# Dot.net
KiCad netlist of a schematic drawn in EAGLE
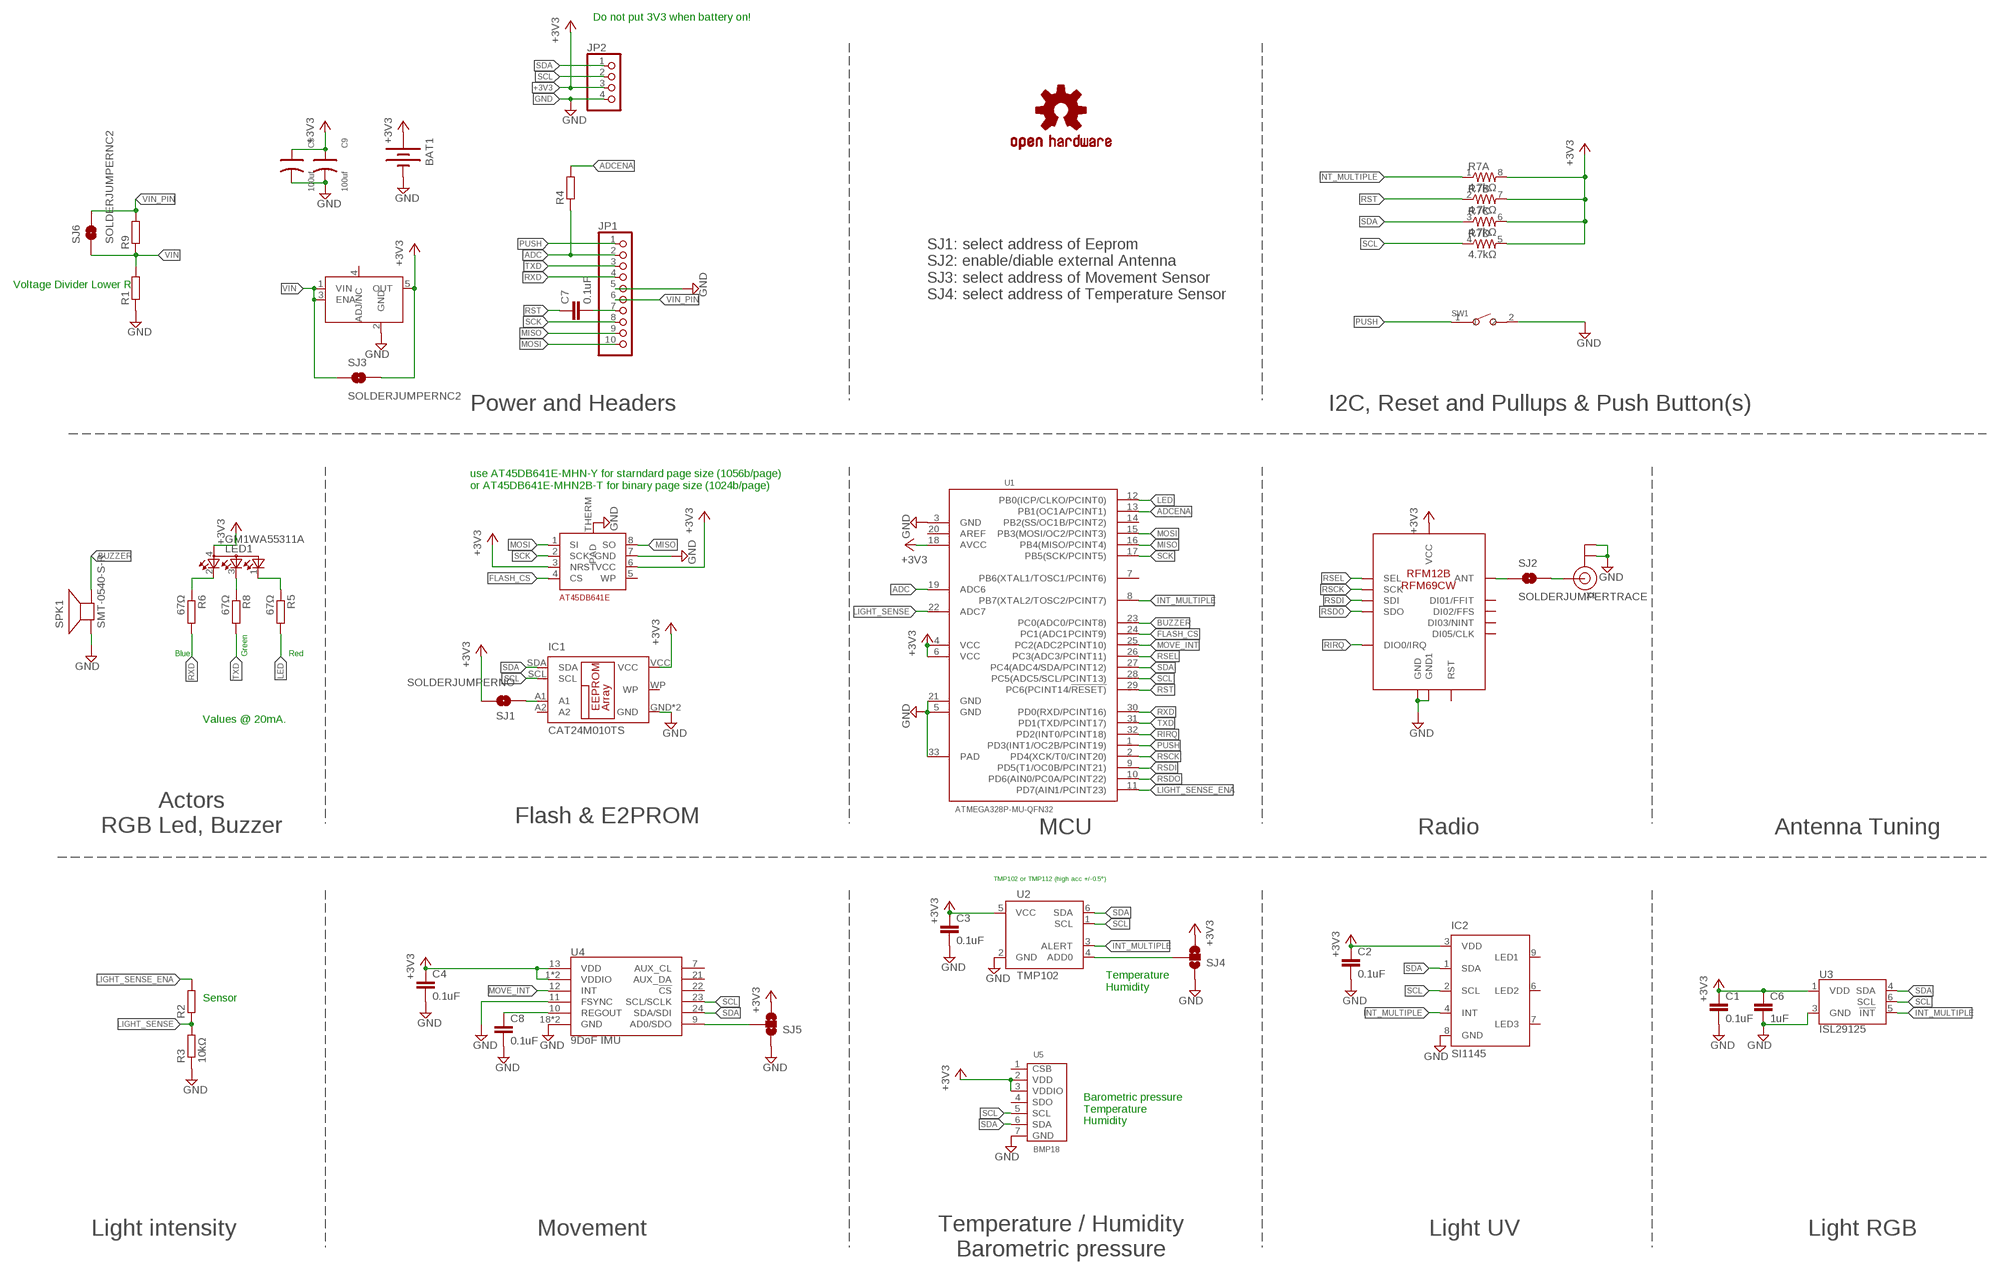
[diagram p0: schematic, sheet 1]
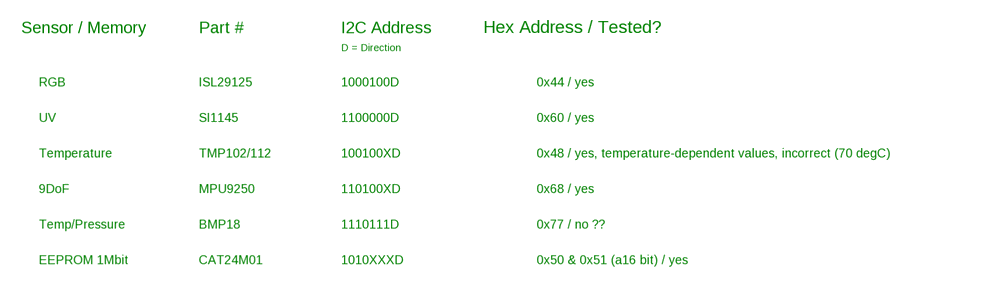
[diagram p1: schematic, sheet 2]
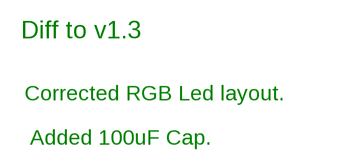
[diagram p2: schematic, sheet 3]

(export (version "E")
  (design (tool "Eeschema 10.0.6"))
  (components
    (comp (ref "BAT1")
      (value "BATTERY20PTH")
      (footprint "eagle-import:BATTCOM_20MM_PTH")
      (libsource (lib "eagle-import") (part "BATTERY20PTH"))
    )
    (comp (ref "C1")
      (value "0.1uF")
      (footprint "eagle-import:C0603")
      (libsource (lib "eagle-import") (part "C-EUC0603"))
    )
    (comp (ref "C2")
      (value "0.1uF")
      (footprint "eagle-import:C0603")
      (libsource (lib "eagle-import") (part "C-EUC0603"))
    )
    (comp (ref "C3")
      (value "0.1uF")
      (footprint "eagle-import:C0603")
      (libsource (lib "eagle-import") (part "C-EUC0603"))
    )
    (comp (ref "C4")
      (value "0.1uF")
      (footprint "eagle-import:C0603")
      (libsource (lib "eagle-import") (part "C-EUC0603"))
    )
    (comp (ref "C5")
      (value "100uf")
      (footprint "eagle-import:AVX-A")
      (fields (field (name "MPN") "TLJA107M006R0800"))
      (libsource (lib "eagle-import") (part "TANTALUM-SMD-100UF-6.3V(AVX-A)"))
    )
    (comp (ref "C6")
      (value "1uF")
      (footprint "eagle-import:C0603")
      (libsource (lib "eagle-import") (part "C-EUC0603"))
    )
    (comp (ref "C7")
      (value "0.1uF")
      (footprint "eagle-import:C0603")
      (libsource (lib "eagle-import") (part "C-EUC0603"))
    )
    (comp (ref "C8")
      (value "0.1uF")
      (footprint "eagle-import:C0603")
      (libsource (lib "eagle-import") (part "C-EUC0603"))
    )
    (comp (ref "C9")
      (value "100uf")
      (footprint "eagle-import:AVX-A")
      (fields (field (name "MPN") "TLJA107M006R0800"))
      (libsource (lib "eagle-import") (part "TANTALUM-SMD-100UF-6.3V(AVX-A)"))
    )
    (comp (ref "IC1")
      (value "CAT24M010TS")
      (footprint "eagle-import:TSSOP8")
      (fields (field (name "MF") "On Semiconductor") (field (name "MPN") "24C00T-E/ST"))
      (libsource (lib "eagle-import") (part "CAT24M01TS0"))
    )
    (comp (ref "IC2")
      (value "SI1145")
      (footprint "eagle-import:QFN-10")
      (libsource (lib "eagle-import") (part "SI1145"))
    )
    (comp (ref "JP1")
      (value "PINHD-1X10")
      (footprint "eagle-import:1X10")
      (libsource (lib "eagle-import") (part "PINHD-1X10"))
    )
    (comp (ref "JP2")
      (value "PINHD-1X4")
      (footprint "eagle-import:1X04")
      (libsource (lib "eagle-import") (part "PINHD-1X4"))
    )
    (comp (ref "LED1")
      (value "GM1WA55311A")
      (footprint "eagle-import:GM1WA55311A")
      (libsource (lib "eagle-import") (part "GM1WA55311A"))
    )
    (comp (ref "LOGO1")
      (value "OSHW-LOGOS")
      (footprint "eagle-import:OSHW-LOGO-S")
      (libsource (lib "eagle-import") (part "OSHW-LOGOS"))
    )
    (comp (ref "R1")
      (value "R-EU_R0603")
      (footprint "eagle-import:R0603")
      (libsource (lib "eagle-import") (part "R-EU_R0603"))
    )
    (comp (ref "R2")
      (value "R-EU_R0805")
      (footprint "eagle-import:R0805")
      (libsource (lib "eagle-import") (part "R-EU_R0805"))
    )
    (comp (ref "R3")
      (value "10kΩ")
      (footprint "eagle-import:R0603")
      (libsource (lib "eagle-import") (part "R-EU_R0603"))
    )
    (comp (ref "R4")
      (value "R-EU_R0603")
      (footprint "eagle-import:R0603")
      (libsource (lib "eagle-import") (part "R-EU_R0603"))
    )
    (comp (ref "R5")
      (value "67Ω")
      (footprint "eagle-import:R0603")
      (libsource (lib "eagle-import") (part "R-EU_R0603"))
    )
    (comp (ref "R6")
      (value "67Ω")
      (footprint "eagle-import:R0603")
      (libsource (lib "eagle-import") (part "R-EU_R0603"))
    )
    (comp (ref "R7")
      (value "4.7kΩ")
      (footprint "eagle-import:0603-ARV")
      (libsource (lib "eagle-import") (part "RESISTOR-ARRAY0603-ARV"))
    )
    (comp (ref "R8")
      (value "67Ω")
      (footprint "eagle-import:R0603")
      (libsource (lib "eagle-import") (part "R-EU_R0603"))
    )
    (comp (ref "R9")
      (value "R-EU_R0603")
      (footprint "eagle-import:R0603")
      (libsource (lib "eagle-import") (part "R-EU_R0603"))
    )
    (comp (ref "SJ1")
      (value "SOLDERJUMPERNO")
      (footprint "eagle-import:SJ_2S-NO")
      (libsource (lib "eagle-import") (part "SOLDERJUMPERNO"))
    )
    (comp (ref "SJ2")
      (value "SOLDERJUMPERTRACE")
      (footprint "eagle-import:SJ_2S-TRACE")
      (libsource (lib "eagle-import") (part "SOLDERJUMPERTRACE"))
    )
    (comp (ref "SJ3")
      (value "SOLDERJUMPERNC2")
      (footprint "eagle-import:SJ_2S-NOTRACE")
      (libsource (lib "eagle-import") (part "SOLDERJUMPERNC2"))
    )
    (comp (ref "SJ4")
      (value "SOLDERJUMPER_2WAYS")
      (footprint "eagle-import:SJ_3")
      (libsource (lib "eagle-import") (part "SOLDERJUMPER_2WAYS"))
    )
    (comp (ref "SJ5")
      (value "SOLDERJUMPER_2WAYS")
      (footprint "eagle-import:SJ_3")
      (libsource (lib "eagle-import") (part "SOLDERJUMPER_2WAYS"))
    )
    (comp (ref "SJ6")
      (value "SOLDERJUMPERNC2")
      (footprint "eagle-import:SJ_2S-NOTRACE")
      (libsource (lib "eagle-import") (part "SOLDERJUMPERNC2"))
    )
    (comp (ref "SPK1")
      (value "SMT-0540-S-R")
      (footprint "eagle-import:SMT-0540-S-R")
      (libsource (lib "eagle-import") (part "SMT-0540-S-R"))
    )
    (comp (ref "SW1")
      (value "SMD-BUTTON(2P-6.0X3.0X2.5MM)-DHT-1163S")
      (footprint "eagle-import:SW2-4.0-6.0X3.0X2.5MM")
      (libsource (lib "eagle-import") (part "SMD-BUTTON(2P-6.0X3.0X2.5MM)-DHT-1163S"))
    )
    (comp (ref "U$1")
      (value "RFM12B/69CW")
      (footprint "eagle-import:RFM12B_69CW")
      (libsource (lib "eagle-import") (part "RFM12B/69CW"))
    )
    (comp (ref "U$3")
      (value "AT45DB641E")
      (footprint "eagle-import:UDFN-8")
      (libsource (lib "eagle-import") (part "AT45DB641E"))
    )
    (comp (ref "U$4")
      (value "LDCL015")
      (footprint "eagle-import:SOT23-5")
      (libsource (lib "eagle-import") (part "LDCL015"))
    )
    (comp (ref "U1")
      (value "ATMEGA328P-MU-QFN32")
      (footprint "eagle-import:QFN32G-0.5-5X5MM")
      (fields (field (name "MPN") "ATMEGA328P-MU"))
      (libsource (lib "eagle-import") (part "MCU-ATMEGA328P-MU(QFN32)"))
    )
    (comp (ref "U2")
      (value "TMP102")
      (footprint "eagle-import:SOT563")
      (libsource (lib "eagle-import") (part "TMP102"))
    )
    (comp (ref "U3")
      (value "ISL29125")
      (footprint "eagle-import:ODFN-6")
      (libsource (lib "eagle-import") (part "ISL29125"))
    )
    (comp (ref "U4")
      (value "9DoF IMU")
      (footprint "eagle-import:QFN24-3X3")
      (libsource (lib "eagle-import") (part "MPU-9250"))
    )
    (comp (ref "U5")
      (value "BMP18")
      (footprint "eagle-import:LGA7-1.5-3.8X3.6MM")
      (libsource (lib "eagle-import") (part "PRESSURE-BMP180(LGA7)"))
    )
    (comp (ref "X1")
      (value "ANTENNA_U.FL")
      (footprint "eagle-import:U.FL")
      (libsource (lib "eagle-import") (part "ANTENNA_U.FL"))
    )
  )
  (nets
    (net (code "1") (name "+3V3") (class "Default")
      (node (ref "BAT1") (pin "1") (pinfunction "+_1") (pintype "power_in"))
      (node (ref "C1") (pin "1") (pinfunction "1_1") (pintype "passive"))
      (node (ref "C2") (pin "1") (pinfunction "1_1") (pintype "passive"))
      (node (ref "C3") (pin "1") (pinfunction "1_1") (pintype "passive"))
      (node (ref "C4") (pin "1") (pinfunction "1_1") (pintype "passive"))
      (node (ref "C5") (pin "+") (pinfunction "+_+") (pintype "passive"))
      (node (ref "C6") (pin "1") (pinfunction "1_1") (pintype "passive"))
      (node (ref "C9") (pin "+") (pinfunction "+_+") (pintype "passive"))
      (node (ref "IC1") (pin "VCC") (pinfunction "VCC_VCC") (pintype "power_in"))
      (node (ref "IC2") (pin "3") (pinfunction "VDD_3") (pintype "power_in"))
      (node (ref "JP2") (pin "3") (pinfunction "3_3") (pintype "passive"))
      (node (ref "LED1") (pin "4") (pinfunction "A_4") (pintype "passive"))
      (node (ref "R7") (pin "5") (pinfunction "2_5") (pintype "passive"))
      (node (ref "R7") (pin "6") (pinfunction "2_6") (pintype "passive"))
      (node (ref "R7") (pin "7") (pinfunction "2_7") (pintype "passive"))
      (node (ref "R7") (pin "8") (pinfunction "2_8") (pintype "passive"))
      (node (ref "SJ1") (pin "2") (pinfunction "2_2") (pintype "passive"))
      (node (ref "SJ3") (pin "2") (pinfunction "2_2") (pintype "passive"))
      (node (ref "SJ4") (pin "3") (pinfunction "3_3") (pintype "passive"))
      (node (ref "SJ5") (pin "3") (pinfunction "3_3") (pintype "passive"))
      (node (ref "U$1") (pin "VDD") (pinfunction "VCC_VDD") (pintype "power_in"))
      (node (ref "U$3") (pin "3") (pinfunction "NRST_3") (pintype "bidirectional"))
      (node (ref "U$3") (pin "6") (pinfunction "VCC_6") (pintype "bidirectional"))
      (node (ref "U$4") (pin "5") (pinfunction "OUT_5") (pintype "bidirectional"))
      (node (ref "U1") (pin "18") (pinfunction "AVCC_18") (pintype "bidirectional"))
      (node (ref "U1") (pin "4") (pinfunction "VCC_4") (pintype "bidirectional"))
      (node (ref "U1") (pin "6") (pinfunction "VCC_6") (pintype "bidirectional"))
      (node (ref "U2") (pin "5") (pinfunction "VCC_5") (pintype "bidirectional"))
      (node (ref "U3") (pin "1") (pinfunction "VDD_1") (pintype "bidirectional"))
      (node (ref "U4") (pin "1") (pinfunction "VDDIO_1") (pintype "bidirectional"))
      (node (ref "U4") (pin "13") (pinfunction "VDD_13") (pintype "bidirectional"))
      (node (ref "U4") (pin "8") (pinfunction "VDDIO_8") (pintype "bidirectional"))
      (node (ref "U5") (pin "2") (pinfunction "VDD_2") (pintype "bidirectional"))
      (node (ref "U5") (pin "3") (pinfunction "VDDIO_3") (pintype "bidirectional"))
    )
    (net (code "2") (name "ADC") (class "Default")
      (node (ref "JP1") (pin "2") (pinfunction "2_2") (pintype "passive"))
      (node (ref "R4") (pin "1") (pinfunction "1_1") (pintype "passive"))
      (node (ref "U1") (pin "19") (pinfunction "ADC6_19") (pintype "bidirectional"))
    )
    (net (code "3") (name "ADCENA") (class "Default")
      (node (ref "R4") (pin "2") (pinfunction "2_2") (pintype "passive"))
      (node (ref "U1") (pin "13") (pinfunction "PB1(OC1A/PCINT1)_13") (pintype "bidirectional"))
    )
    (net (code "4") (name "BUZZER") (class "Default")
      (node (ref "SPK1") (pin "+") (pinfunction "-_+") (pintype "passive"))
      (node (ref "U1") (pin "23") (pinfunction "PC0(ADC0/PCINT8)_23") (pintype "bidirectional"))
    )
    (net (code "5") (name "FLASH_CS") (class "Default")
      (node (ref "U$3") (pin "4") (pinfunction "CS_4") (pintype "bidirectional"))
      (node (ref "U1") (pin "24") (pinfunction "PC1(ADC1PCINT9)_24") (pintype "bidirectional"))
    )
    (net (code "6") (name "GND") (class "Default")
      (node (ref "BAT1") (pin "2") (pinfunction "-_2") (pintype "power_in"))
      (node (ref "C1") (pin "2") (pinfunction "2_2") (pintype "passive"))
      (node (ref "C2") (pin "2") (pinfunction "2_2") (pintype "passive"))
      (node (ref "C3") (pin "2") (pinfunction "2_2") (pintype "passive"))
      (node (ref "C4") (pin "2") (pinfunction "2_2") (pintype "passive"))
      (node (ref "C5") (pin "-") (pinfunction "-_-") (pintype "passive"))
      (node (ref "C6") (pin "2") (pinfunction "2_2") (pintype "passive"))
      (node (ref "C8") (pin "2") (pinfunction "2_2") (pintype "passive"))
      (node (ref "C9") (pin "-") (pinfunction "-_-") (pintype "passive"))
      (node (ref "IC1") (pin "GND") (pinfunction "GND_GND") (pintype "power_in"))
      (node (ref "IC1") (pin "NC") (pinfunction "GND_NC") (pintype "power_in"))
      (node (ref "IC2") (pin "8") (pinfunction "GND_8") (pintype "power_in"))
      (node (ref "JP1") (pin "5") (pinfunction "5_5") (pintype "passive"))
      (node (ref "JP2") (pin "4") (pinfunction "4_4") (pintype "passive"))
      (node (ref "R1") (pin "1") (pinfunction "1_1") (pintype "passive"))
      (node (ref "R3") (pin "1") (pinfunction "1_1") (pintype "passive"))
      (node (ref "SJ4") (pin "1") (pinfunction "1_1") (pintype "passive"))
      (node (ref "SJ5") (pin "1") (pinfunction "1_1") (pintype "passive"))
      (node (ref "SPK1") (pin "-") (pinfunction "+_-") (pintype "passive"))
      (node (ref "SW1") (pin "2") (pinfunction "2_2") (pintype "bidirectional"))
      (node (ref "U$1") (pin "GND") (pinfunction "GND_GND") (pintype "power_in"))
      (node (ref "U$1") (pin "GND1") (pinfunction "GND1_GND1") (pintype "power_in"))
      (node (ref "U$3") (pin "7") (pinfunction "GND_7") (pintype "bidirectional"))
      (node (ref "U$3") (pin "THERM") (pinfunction "PAD_THERM") (pintype "bidirectional"))
      (node (ref "U$4") (pin "2") (pinfunction "GND_2") (pintype "bidirectional"))
      (node (ref "U1") (pin "21") (pinfunction "GND_21") (pintype "bidirectional"))
      (node (ref "U1") (pin "3") (pinfunction "GND_3") (pintype "bidirectional"))
      (node (ref "U1") (pin "33") (pinfunction "PAD_33") (pintype "bidirectional"))
      (node (ref "U1") (pin "5") (pinfunction "GND_5") (pintype "bidirectional"))
      (node (ref "U2") (pin "2") (pinfunction "GND_2") (pintype "bidirectional"))
      (node (ref "U3") (pin "3") (pinfunction "GND_3") (pintype "bidirectional"))
      (node (ref "U4") (pin "11") (pinfunction "FSYNC_11") (pintype "bidirectional"))
      (node (ref "U4") (pin "18") (pinfunction "GND_18") (pintype "bidirectional"))
      (node (ref "U4") (pin "20") (pinfunction "GND_20") (pintype "bidirectional"))
      (node (ref "U5") (pin "7") (pinfunction "GND_7") (pintype "bidirectional"))
      (node (ref "X1") (pin "1") (pinfunction "GND_1") (pintype "passive"))
      (node (ref "X1") (pin "2") (pinfunction "GND_2") (pintype "passive"))
    )
    (net (code "7") (name "INT_MULTIPLE") (class "Default")
      (node (ref "IC2") (pin "4") (pinfunction "INT_4") (pintype "open_collector"))
      (node (ref "R7") (pin "1") (pinfunction "1_1") (pintype "passive"))
      (node (ref "U1") (pin "8") (pinfunction "PB7(XTAL2/TOSC2/PCINT7)_8") (pintype "bidirectional"))
      (node (ref "U2") (pin "3") (pinfunction "ALERT_3") (pintype "bidirectional"))
      (node (ref "U3") (pin "5") (pinfunction "~{INT}_5") (pintype "bidirectional"))
    )
    (net (code "8") (name "LED") (class "Default")
      (node (ref "R5") (pin "2") (pinfunction "2_2") (pintype "passive"))
      (node (ref "U1") (pin "12") (pinfunction "PB0(ICP/CLKO/PCINT0)_12") (pintype "bidirectional"))
    )
    (net (code "9") (name "LIGHT_SENSE") (class "Default")
      (node (ref "R2") (pin "1") (pinfunction "1_1") (pintype "passive"))
      (node (ref "R3") (pin "2") (pinfunction "2_2") (pintype "passive"))
      (node (ref "U1") (pin "22") (pinfunction "ADC7_22") (pintype "bidirectional"))
    )
    (net (code "10") (name "LIGHT_SENSE_ENA") (class "Default")
      (node (ref "R2") (pin "2") (pinfunction "2_2") (pintype "passive"))
      (node (ref "U1") (pin "11") (pinfunction "PD7(AIN1/PCINT23)_11") (pintype "bidirectional"))
    )
    (net (code "11") (name "MISO") (class "Default")
      (node (ref "JP1") (pin "9") (pinfunction "9_9") (pintype "passive"))
      (node (ref "U$3") (pin "8") (pinfunction "SO_8") (pintype "bidirectional"))
      (node (ref "U1") (pin "16") (pinfunction "PB4(MISO/PCINT4)_16") (pintype "bidirectional"))
    )
    (net (code "12") (name "MOSI") (class "Default")
      (node (ref "JP1") (pin "10") (pinfunction "10_10") (pintype "passive"))
      (node (ref "U$3") (pin "1") (pinfunction "SI_1") (pintype "bidirectional"))
      (node (ref "U1") (pin "15") (pinfunction "PB3(MOSI/OC2/PCINT3)_15") (pintype "bidirectional"))
    )
    (net (code "13") (name "MOVE_INT") (class "Default")
      (node (ref "U1") (pin "25") (pinfunction "PC2(ADC2PCINT10)_25") (pintype "bidirectional"))
      (node (ref "U4") (pin "12") (pinfunction "INT_12") (pintype "bidirectional"))
    )
    (net (code "14") (name "Net-(C7-Pad2)") (class "Default")
      (node (ref "C7") (pin "2") (pinfunction "2_2") (pintype "passive"))
      (node (ref "JP1") (pin "7") (pinfunction "7_7") (pintype "passive"))
    )
    (net (code "15") (name "Net-(IC1-PadA1)") (class "Default")
      (node (ref "IC1") (pin "A1") (pinfunction "A1_A1") (pintype "bidirectional"))
      (node (ref "SJ1") (pin "1") (pinfunction "1_1") (pintype "passive"))
    )
    (net (code "16") (name "Net-(LED1-CBLUE)") (class "Default")
      (node (ref "LED1") (pin "3") (pinfunction "CBLUE_3") (pintype "passive"))
      (node (ref "R8") (pin "1") (pinfunction "1_1") (pintype "passive"))
    )
    (net (code "17") (name "Net-(LED1-CGREEN)") (class "Default")
      (node (ref "LED1") (pin "1") (pinfunction "CGREEN_1") (pintype "passive"))
      (node (ref "R5") (pin "1") (pinfunction "1_1") (pintype "passive"))
    )
    (net (code "18") (name "Net-(LED1-CRED)") (class "Default")
      (node (ref "LED1") (pin "2") (pinfunction "CRED_2") (pintype "passive"))
      (node (ref "R6") (pin "1") (pinfunction "1_1") (pintype "passive"))
    )
    (net (code "19") (name "Net-(SJ2-Pad1)") (class "Default")
      (node (ref "SJ2") (pin "1") (pinfunction "1_1") (pintype "passive"))
      (node (ref "U$1") (pin "ANT") (pinfunction "ANT_ANT") (pintype "passive"))
    )
    (net (code "20") (name "Net-(U2-ADD0)") (class "Default")
      (node (ref "SJ4") (pin "2") (pinfunction "2_2") (pintype "passive"))
      (node (ref "U2") (pin "4") (pinfunction "ADD0_4") (pintype "bidirectional"))
    )
    (net (code "21") (name "Net-(U4-AD0{slash}SDO)") (class "Default")
      (node (ref "SJ5") (pin "2") (pinfunction "2_2") (pintype "passive"))
      (node (ref "U4") (pin "9") (pinfunction "AD0/SDO_9") (pintype "bidirectional"))
    )
    (net (code "22") (name "Net-(U4-REGOUT)") (class "Default")
      (node (ref "C8") (pin "1") (pinfunction "1_1") (pintype "passive"))
      (node (ref "U4") (pin "10") (pinfunction "REGOUT_10") (pintype "bidirectional"))
    )
    (net (code "23") (name "Net-(X1-SIGNAL)") (class "Default")
      (node (ref "SJ2") (pin "2") (pinfunction "2_2") (pintype "passive"))
      (node (ref "X1") (pin "3") (pinfunction "SIGNAL_3") (pintype "passive"))
    )
    (net (code "24") (name "PUSH") (class "Default")
      (node (ref "JP1") (pin "1") (pinfunction "1_1") (pintype "passive"))
      (node (ref "SW1") (pin "1") (pinfunction "1_1") (pintype "bidirectional"))
      (node (ref "U1") (pin "1") (pinfunction "PD3(INT1/OC2B/PCINT19)_1") (pintype "bidirectional"))
    )
    (net (code "25") (name "RIRQ") (class "Default")
      (node (ref "U$1") (pin "IRQ") (pinfunction "DIO0/IRQ_IRQ") (pintype "open_collector"))
      (node (ref "U1") (pin "32") (pinfunction "PD2(INT0/PCINT18)_32") (pintype "bidirectional"))
    )
    (net (code "26") (name "RSCK") (class "Default")
      (node (ref "U$1") (pin "SCK") (pinfunction "SCK_SCK") (pintype "input"))
      (node (ref "U1") (pin "2") (pinfunction "PD4(XCK/T0/CINT20)_2") (pintype "bidirectional"))
    )
    (net (code "27") (name "RSDI") (class "Default")
      (node (ref "U$1") (pin "SDI") (pinfunction "SDI_SDI") (pintype "input"))
      (node (ref "U1") (pin "9") (pinfunction "PD5(T1/OC0B/PCINT21)_9") (pintype "bidirectional"))
    )
    (net (code "28") (name "RSDO") (class "Default")
      (node (ref "U$1") (pin "SDO") (pinfunction "SDO_SDO") (pintype "output"))
      (node (ref "U1") (pin "10") (pinfunction "PD6(AIN0/PC0A/PCINT22)_10") (pintype "bidirectional"))
    )
    (net (code "29") (name "RSEL") (class "Default")
      (node (ref "U$1") (pin "SEL") (pinfunction "SEL_SEL") (pintype "input"))
      (node (ref "U1") (pin "26") (pinfunction "PC3(ADC3/PCINT11)_26") (pintype "bidirectional"))
    )
    (net (code "30") (name "RST") (class "Default")
      (node (ref "C7") (pin "1") (pinfunction "1_1") (pintype "passive"))
      (node (ref "R7") (pin "2") (pinfunction "1_2") (pintype "passive"))
      (node (ref "U1") (pin "29") (pinfunction "PC6(PCINT14/~{RESET})_29") (pintype "bidirectional"))
    )
    (net (code "31") (name "RXD") (class "Default")
      (node (ref "JP1") (pin "4") (pinfunction "4_4") (pintype "passive"))
      (node (ref "R6") (pin "2") (pinfunction "2_2") (pintype "passive"))
      (node (ref "U1") (pin "30") (pinfunction "PD0(RXD/PCINT16)_30") (pintype "bidirectional"))
    )
    (net (code "32") (name "SCK") (class "Default")
      (node (ref "JP1") (pin "8") (pinfunction "8_8") (pintype "passive"))
      (node (ref "U$3") (pin "2") (pinfunction "SCK_2") (pintype "bidirectional"))
      (node (ref "U1") (pin "17") (pinfunction "PB5(SCK/PCINT5)_17") (pintype "bidirectional"))
    )
    (net (code "33") (name "SCL") (class "Default")
      (node (ref "IC1") (pin "SCL") (pinfunction "SCL_SCL") (pintype "input"))
      (node (ref "IC2") (pin "2") (pinfunction "SCL_2") (pintype "input"))
      (node (ref "JP2") (pin "2") (pinfunction "2_2") (pintype "passive"))
      (node (ref "R7") (pin "4") (pinfunction "1_4") (pintype "passive"))
      (node (ref "U1") (pin "28") (pinfunction "PC5(ADC5/SCL/PCINT13)_28") (pintype "bidirectional"))
      (node (ref "U2") (pin "1") (pinfunction "SCL_1") (pintype "bidirectional"))
      (node (ref "U3") (pin "6") (pinfunction "SCL_6") (pintype "bidirectional"))
      (node (ref "U4") (pin "23") (pinfunction "SCL/SCLK_23") (pintype "bidirectional"))
      (node (ref "U5") (pin "5") (pinfunction "SCL_5") (pintype "bidirectional"))
    )
    (net (code "34") (name "SDA") (class "Default")
      (node (ref "IC1") (pin "SDA") (pinfunction "SDA_SDA") (pintype "bidirectional"))
      (node (ref "IC2") (pin "1") (pinfunction "SDA_1") (pintype "bidirectional"))
      (node (ref "JP2") (pin "1") (pinfunction "1_1") (pintype "passive"))
      (node (ref "R7") (pin "3") (pinfunction "1_3") (pintype "passive"))
      (node (ref "U1") (pin "27") (pinfunction "PC4(ADC4/SDA/PCINT12)_27") (pintype "bidirectional"))
      (node (ref "U2") (pin "6") (pinfunction "SDA_6") (pintype "bidirectional"))
      (node (ref "U3") (pin "4") (pinfunction "SDA_4") (pintype "bidirectional"))
      (node (ref "U4") (pin "24") (pinfunction "SDA/SDI_24") (pintype "bidirectional"))
      (node (ref "U5") (pin "6") (pinfunction "SDA_6") (pintype "bidirectional"))
    )
    (net (code "35") (name "TXD") (class "Default")
      (node (ref "JP1") (pin "3") (pinfunction "3_3") (pintype "passive"))
      (node (ref "R8") (pin "2") (pinfunction "2_2") (pintype "passive"))
      (node (ref "U1") (pin "31") (pinfunction "PD1(TXD/PCINT17)_31") (pintype "bidirectional"))
    )
    (net (code "36") (name "VIN") (class "Default")
      (node (ref "R1") (pin "2") (pinfunction "2_2") (pintype "passive"))
      (node (ref "R9") (pin "1") (pinfunction "1_1") (pintype "passive"))
      (node (ref "SJ3") (pin "1") (pinfunction "1_1") (pintype "passive"))
      (node (ref "SJ6") (pin "1") (pinfunction "1_1") (pintype "passive"))
      (node (ref "U$4") (pin "1") (pinfunction "VIN_1") (pintype "bidirectional"))
      (node (ref "U$4") (pin "3") (pinfunction "ENA_3") (pintype "bidirectional"))
    )
    (net (code "37") (name "VIN_PIN") (class "Default")
      (node (ref "JP1") (pin "6") (pinfunction "6_6") (pintype "passive"))
      (node (ref "R9") (pin "2") (pinfunction "2_2") (pintype "passive"))
      (node (ref "SJ6") (pin "2") (pinfunction "2_2") (pintype "passive"))
    )
    (net (code "38") (name "unconnected-(IC1-PadA2)") (class "Default")
      (node (ref "IC1") (pin "A2") (pinfunction "A2_A2") (pintype "bidirectional"))
    )
    (net (code "39") (name "unconnected-(IC1-PadWP)") (class "Default")
      (node (ref "IC1") (pin "WP") (pinfunction "WP_WP") (pintype "bidirectional"))
    )
    (net (code "40") (name "unconnected-(IC2-LED1-Pad9)") (class "Default")
      (node (ref "IC2") (pin "9") (pinfunction "LED1_9") (pintype "output"))
    )
    (net (code "41") (name "unconnected-(IC2-LED2-Pad6)") (class "Default")
      (node (ref "IC2") (pin "6") (pinfunction "LED2_6") (pintype "output"))
    )
    (net (code "42") (name "unconnected-(IC2-LED3-Pad7)") (class "Default")
      (node (ref "IC2") (pin "7") (pinfunction "LED3_7") (pintype "output"))
    )
    (net (code "43") (name "unconnected-(U$1-DI01{slash}FFIT-PadFFIT)") (class "Default")
      (node (ref "U$1") (pin "FFIT") (pinfunction "DI01/FFIT_FFIT") (pintype "passive"))
    )
    (net (code "44") (name "unconnected-(U$1-DI02{slash}FFS-PadFFS)") (class "Default")
      (node (ref "U$1") (pin "FFS") (pinfunction "DI02/FFS_FFS") (pintype "bidirectional"))
    )
    (net (code "45") (name "unconnected-(U$1-DI03{slash}NINT-PadNINT)") (class "Default")
      (node (ref "U$1") (pin "NINT") (pinfunction "DI03/NINT_NINT") (pintype "passive"))
    )
    (net (code "46") (name "unconnected-(U$1-DI05{slash}CLK-PadCLK)") (class "Default")
      (node (ref "U$1") (pin "CLK") (pinfunction "DI05/CLK_CLK") (pintype "passive"))
    )
    (net (code "47") (name "unconnected-(U$1-PadRST)") (class "Default")
      (node (ref "U$1") (pin "RST") (pinfunction "RST_RST") (pintype "open_collector"))
    )
    (net (code "48") (name "unconnected-(U$3-WP-Pad5)") (class "Default")
      (node (ref "U$3") (pin "5") (pinfunction "WP_5") (pintype "bidirectional"))
    )
    (net (code "49") (name "unconnected-(U$4-ADJ{slash}NC-Pad4)") (class "Default")
      (node (ref "U$4") (pin "4") (pinfunction "ADJ/NC_4") (pintype "bidirectional"))
    )
    (net (code "50") (name "unconnected-(U1-AREF-Pad20)") (class "Default")
      (node (ref "U1") (pin "20") (pinfunction "AREF_20") (pintype "bidirectional"))
    )
    (net (code "51") (name "unconnected-(U1-PB2(SS{slash}OC1B{slash}PCINT2)-Pad14)") (class "Default")
      (node (ref "U1") (pin "14") (pinfunction "PB2(SS/OC1B/PCINT2)_14") (pintype "bidirectional"))
    )
    (net (code "52") (name "unconnected-(U1-PB6(XTAL1{slash}TOSC1{slash}PCINT6)-Pad7)") (class "Default")
      (node (ref "U1") (pin "7") (pinfunction "PB6(XTAL1/TOSC1/PCINT6)_7") (pintype "bidirectional"))
    )
    (net (code "53") (name "unconnected-(U4-AUX_CL-Pad7)") (class "Default")
      (node (ref "U4") (pin "7") (pinfunction "AUX_CL_7") (pintype "bidirectional"))
    )
    (net (code "54") (name "unconnected-(U4-AUX_DA-Pad21)") (class "Default")
      (node (ref "U4") (pin "21") (pinfunction "AUX_DA_21") (pintype "bidirectional"))
    )
    (net (code "55") (name "unconnected-(U4-~{CS}-Pad22)") (class "Default")
      (node (ref "U4") (pin "22") (pinfunction "~{CS}_22") (pintype "bidirectional"))
    )
    (net (code "56") (name "unconnected-(U5-CSB-Pad1)") (class "Default")
      (node (ref "U5") (pin "1") (pinfunction "CSB_1") (pintype "bidirectional"))
    )
    (net (code "57") (name "unconnected-(U5-SDO-Pad4)") (class "Default")
      (node (ref "U5") (pin "4") (pinfunction "SDO_4") (pintype "bidirectional"))
    )
  )
)
